# Breadboard_Breakout_Module.net
KiCad netlist of a schematic drawn in EAGLE
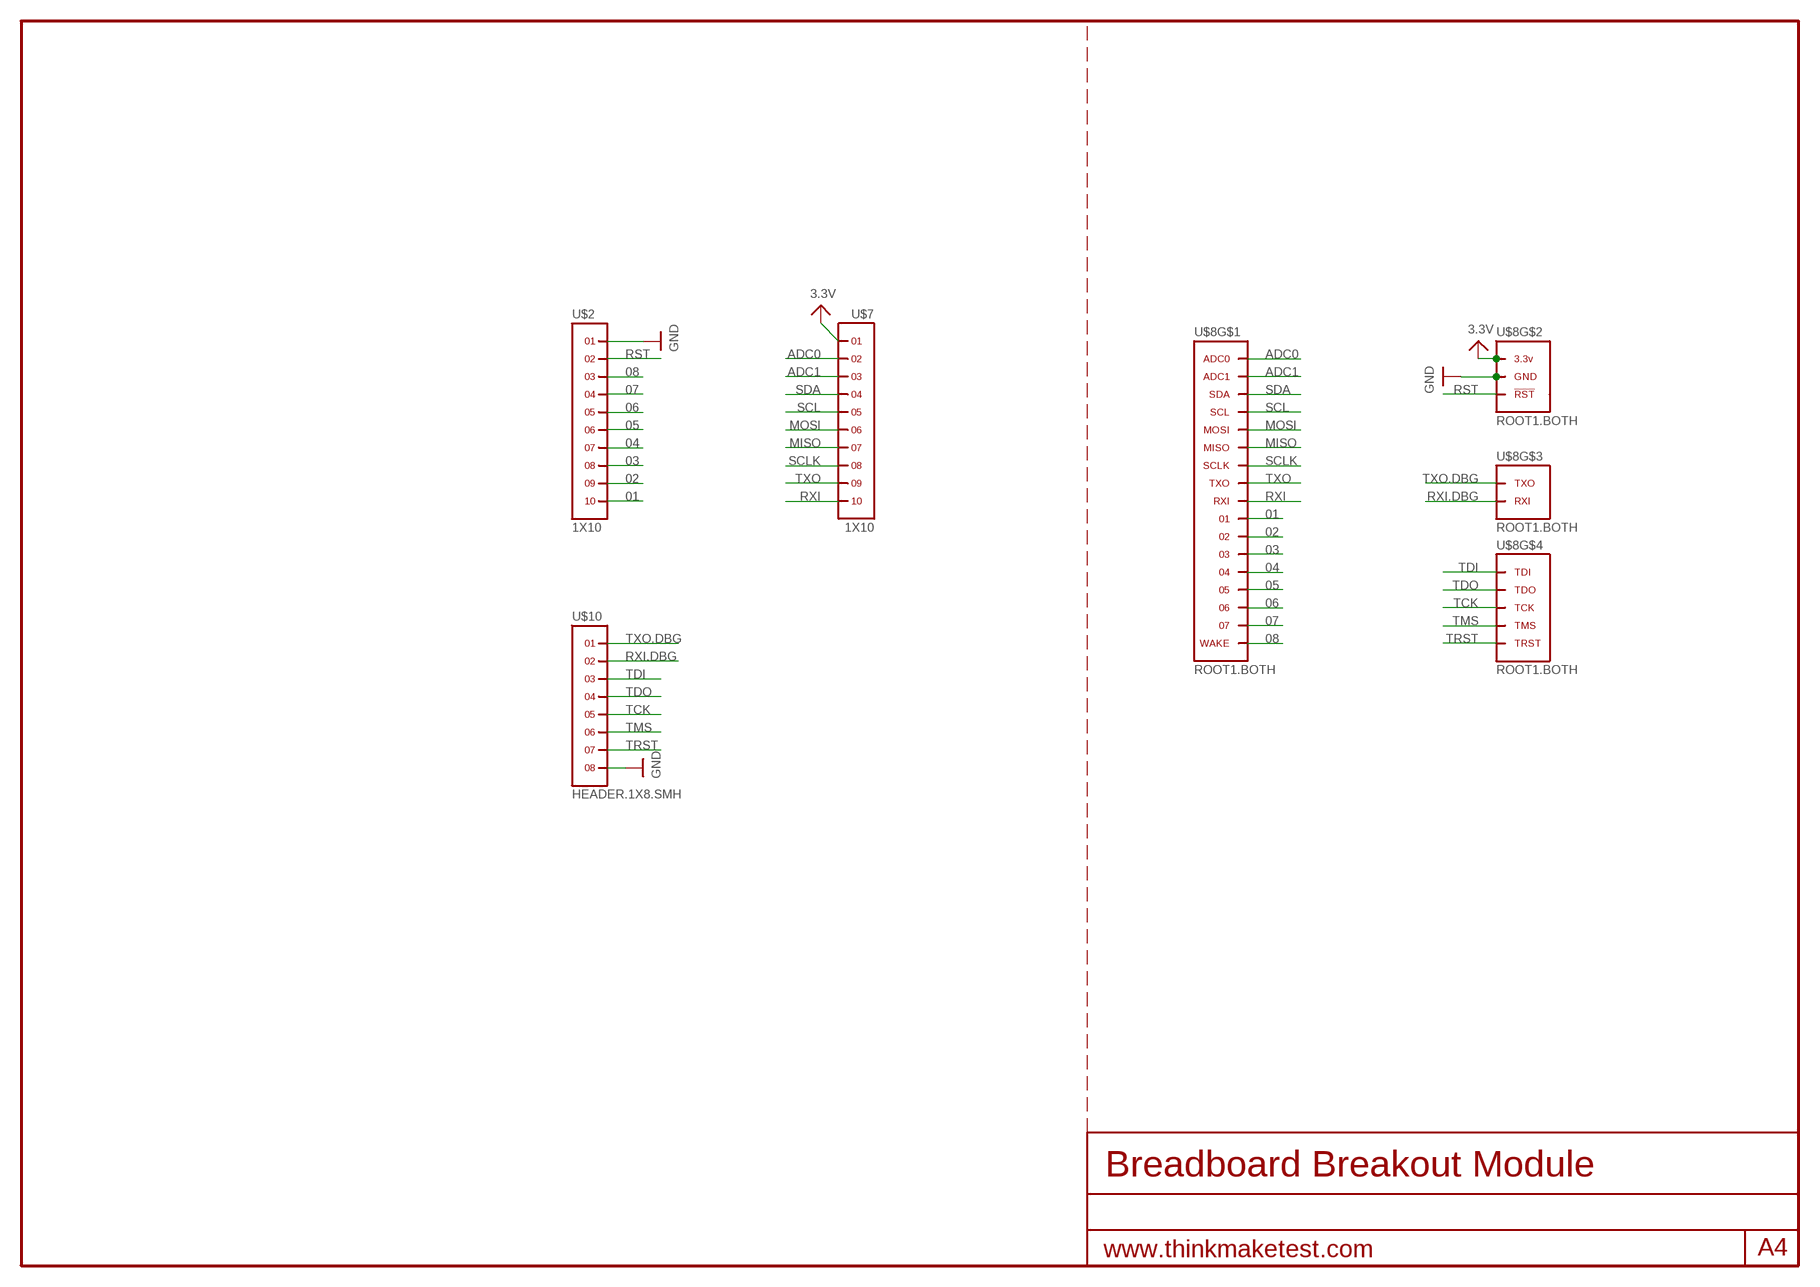
[diagram p0: schematic, sheet 1]

(export (version "E")
  (design (tool "Eeschema 10.0.6"))
  (components
    (comp (ref "U$2")
      (value "1X10")
      (footprint "eagle-import:1X10")
      (libsource (lib "eagle-import") (part "1X10"))
    )
    (comp (ref "U$7")
      (value "1X10")
      (footprint "eagle-import:1X10")
      (libsource (lib "eagle-import") (part "1X10"))
    )
    (comp (ref "U$8")
      (value "ROOT1.BOTH")
      (footprint "eagle-import:ROOT1.BOTH")
      (libsource (lib "eagle-import") (part "ROOT1.BOTH"))
    )
    (comp (ref "U$10")
      (value "HEADER.1X8.SMH")
      (footprint "eagle-import:SMH-108-XX-X-S")
      (libsource (lib "eagle-import") (part "HEADER.1X8.SMH"))
    )
  )
  (nets
    (net (code "1") (name "/01") (class "Default")
      (node (ref "U$2") (pin "10") (pinfunction "10_10") (pintype "bidirectional"))
      (node (ref "U$8") (pin "01") (pinfunction "01_01") (pintype "bidirectional"))
      (node (ref "U$8") (pin "01@1") (pinfunction "01_01@1") (pintype "bidirectional"))
      (node (ref "U$8") (pin "01@VIA") (pinfunction "01_01@VIA") (pintype "bidirectional"))
    )
    (net (code "2") (name "/02") (class "Default")
      (node (ref "U$2") (pin "9") (pinfunction "9_9") (pintype "bidirectional"))
      (node (ref "U$8") (pin "02") (pinfunction "02_02") (pintype "bidirectional"))
      (node (ref "U$8") (pin "02@1") (pinfunction "02_02@1") (pintype "bidirectional"))
      (node (ref "U$8") (pin "02@VIA") (pinfunction "02_02@VIA") (pintype "bidirectional"))
    )
    (net (code "3") (name "/03") (class "Default")
      (node (ref "U$2") (pin "8") (pinfunction "8_8") (pintype "bidirectional"))
      (node (ref "U$8") (pin "03") (pinfunction "03_03") (pintype "bidirectional"))
      (node (ref "U$8") (pin "03@1") (pinfunction "03_03@1") (pintype "bidirectional"))
      (node (ref "U$8") (pin "03@VIA") (pinfunction "03_03@VIA") (pintype "bidirectional"))
    )
    (net (code "4") (name "/04") (class "Default")
      (node (ref "U$2") (pin "7") (pinfunction "7_7") (pintype "bidirectional"))
      (node (ref "U$8") (pin "04") (pinfunction "04_04") (pintype "bidirectional"))
      (node (ref "U$8") (pin "04@1") (pinfunction "04_04@1") (pintype "bidirectional"))
      (node (ref "U$8") (pin "04@VIA") (pinfunction "04_04@VIA") (pintype "bidirectional"))
    )
    (net (code "5") (name "/05") (class "Default")
      (node (ref "U$2") (pin "6") (pinfunction "6_6") (pintype "bidirectional"))
      (node (ref "U$8") (pin "05") (pinfunction "05_05") (pintype "bidirectional"))
      (node (ref "U$8") (pin "05@1") (pinfunction "05_05@1") (pintype "bidirectional"))
      (node (ref "U$8") (pin "05@VIA") (pinfunction "05_05@VIA") (pintype "bidirectional"))
    )
    (net (code "6") (name "/06") (class "Default")
      (node (ref "U$2") (pin "5") (pinfunction "5_5") (pintype "bidirectional"))
      (node (ref "U$8") (pin "06") (pinfunction "06_06") (pintype "bidirectional"))
      (node (ref "U$8") (pin "06@1") (pinfunction "06_06@1") (pintype "bidirectional"))
      (node (ref "U$8") (pin "06@VIA") (pinfunction "06_06@VIA") (pintype "bidirectional"))
    )
    (net (code "7") (name "/07") (class "Default")
      (node (ref "U$2") (pin "4") (pinfunction "4_4") (pintype "bidirectional"))
      (node (ref "U$8") (pin "07") (pinfunction "07_07") (pintype "bidirectional"))
      (node (ref "U$8") (pin "07@1") (pinfunction "07_07@1") (pintype "bidirectional"))
      (node (ref "U$8") (pin "07@VIA") (pinfunction "07_07@VIA") (pintype "bidirectional"))
    )
    (net (code "8") (name "/08") (class "Default")
      (node (ref "U$2") (pin "3") (pinfunction "3_3") (pintype "bidirectional"))
      (node (ref "U$8") (pin "WAKE") (pinfunction "WAKE_WAKE") (pintype "bidirectional"))
      (node (ref "U$8") (pin "WAKE@1") (pinfunction "WAKE_WAKE@1") (pintype "bidirectional"))
      (node (ref "U$8") (pin "WAKE@VIA") (pinfunction "WAKE_WAKE@VIA") (pintype "bidirectional"))
    )
    (net (code "9") (name "/ADC0") (class "Default")
      (node (ref "U$7") (pin "2") (pinfunction "2_2") (pintype "bidirectional"))
      (node (ref "U$8") (pin "ADC0") (pinfunction "ADC0_ADC0") (pintype "bidirectional"))
      (node (ref "U$8") (pin "ADC0@1") (pinfunction "ADC0_ADC0@1") (pintype "bidirectional"))
      (node (ref "U$8") (pin "ADC0@VIA") (pinfunction "ADC0_ADC0@VIA") (pintype "bidirectional"))
    )
    (net (code "10") (name "/ADC1") (class "Default")
      (node (ref "U$7") (pin "3") (pinfunction "3_3") (pintype "bidirectional"))
      (node (ref "U$8") (pin "ADC1") (pinfunction "ADC1_ADC1") (pintype "bidirectional"))
      (node (ref "U$8") (pin "ADC1@1") (pinfunction "ADC1_ADC1@1") (pintype "bidirectional"))
      (node (ref "U$8") (pin "ADC1@VIA") (pinfunction "ADC1_ADC1@VIA") (pintype "bidirectional"))
    )
    (net (code "11") (name "/MISO") (class "Default")
      (node (ref "U$7") (pin "7") (pinfunction "7_7") (pintype "bidirectional"))
      (node (ref "U$8") (pin "MISO") (pinfunction "MISO_MISO") (pintype "bidirectional"))
      (node (ref "U$8") (pin "MISO@1") (pinfunction "MISO_MISO@1") (pintype "bidirectional"))
      (node (ref "U$8") (pin "MISO@VIA") (pinfunction "MISO_MISO@VIA") (pintype "bidirectional"))
    )
    (net (code "12") (name "/MOSI") (class "Default")
      (node (ref "U$7") (pin "6") (pinfunction "6_6") (pintype "bidirectional"))
      (node (ref "U$8") (pin "MOSI") (pinfunction "MOSI_MOSI") (pintype "bidirectional"))
      (node (ref "U$8") (pin "MOSI@1") (pinfunction "MOSI_MOSI@1") (pintype "bidirectional"))
      (node (ref "U$8") (pin "MOSI@VIA") (pinfunction "MOSI_MOSI@VIA") (pintype "bidirectional"))
    )
    (net (code "13") (name "/RST") (class "Default")
      (node (ref "U$2") (pin "2") (pinfunction "2_2") (pintype "bidirectional"))
      (node (ref "U$8") (pin "RST") (pinfunction "~{RST}_RST") (pintype "bidirectional"))
      (node (ref "U$8") (pin "RST@1") (pinfunction "~{RST}_RST@1") (pintype "bidirectional"))
      (node (ref "U$8") (pin "RST@VIA") (pinfunction "~{RST}_RST@VIA") (pintype "bidirectional"))
    )
    (net (code "14") (name "/RXI") (class "Default")
      (node (ref "U$7") (pin "10") (pinfunction "10_10") (pintype "bidirectional"))
      (node (ref "U$8") (pin "RXI") (pinfunction "RXI_RXI") (pintype "bidirectional"))
      (node (ref "U$8") (pin "RXI@1") (pinfunction "RXI_RXI@1") (pintype "bidirectional"))
      (node (ref "U$8") (pin "RXI@VIA") (pinfunction "RXI_RXI@VIA") (pintype "bidirectional"))
    )
    (net (code "15") (name "/RXI.DBG") (class "Default")
      (node (ref "U$10") (pin "2") (pinfunction "2_2") (pintype "bidirectional"))
      (node (ref "U$8") (pin "RXI.DBG") (pinfunction "RXI_RXI.DBG") (pintype "bidirectional"))
      (node (ref "U$8") (pin "RXI.DBG@1") (pinfunction "RXI_RXI.DBG@1") (pintype "bidirectional"))
      (node (ref "U$8") (pin "RXI.DBG@VIA") (pinfunction "RXI_RXI.DBG@VIA") (pintype "bidirectional"))
    )
    (net (code "16") (name "/SCL") (class "Default")
      (node (ref "U$7") (pin "5") (pinfunction "5_5") (pintype "bidirectional"))
      (node (ref "U$8") (pin "SCL") (pinfunction "SCL_SCL") (pintype "bidirectional"))
      (node (ref "U$8") (pin "SCL@1") (pinfunction "SCL_SCL@1") (pintype "bidirectional"))
      (node (ref "U$8") (pin "SCL@VIA") (pinfunction "SCL_SCL@VIA") (pintype "bidirectional"))
    )
    (net (code "17") (name "/SCLK") (class "Default")
      (node (ref "U$7") (pin "8") (pinfunction "8_8") (pintype "bidirectional"))
      (node (ref "U$8") (pin "SCLK") (pinfunction "SCLK_SCLK") (pintype "bidirectional"))
      (node (ref "U$8") (pin "SCLK@1") (pinfunction "SCLK_SCLK@1") (pintype "bidirectional"))
      (node (ref "U$8") (pin "SCLK@VIA") (pinfunction "SCLK_SCLK@VIA") (pintype "bidirectional"))
    )
    (net (code "18") (name "/SDA") (class "Default")
      (node (ref "U$7") (pin "4") (pinfunction "4_4") (pintype "bidirectional"))
      (node (ref "U$8") (pin "SDA") (pinfunction "SDA_SDA") (pintype "bidirectional"))
      (node (ref "U$8") (pin "SDA@1") (pinfunction "SDA_SDA@1") (pintype "bidirectional"))
      (node (ref "U$8") (pin "SDA@VIA") (pinfunction "SDA_SDA@VIA") (pintype "bidirectional"))
    )
    (net (code "19") (name "/TCK") (class "Default")
      (node (ref "U$10") (pin "5") (pinfunction "5_5") (pintype "bidirectional"))
      (node (ref "U$8") (pin "TCK") (pinfunction "TCK_TCK") (pintype "bidirectional"))
      (node (ref "U$8") (pin "TCK@1") (pinfunction "TCK_TCK@1") (pintype "bidirectional"))
      (node (ref "U$8") (pin "TCK@VIA") (pinfunction "TCK_TCK@VIA") (pintype "bidirectional"))
    )
    (net (code "20") (name "/TDI") (class "Default")
      (node (ref "U$10") (pin "3") (pinfunction "3_3") (pintype "bidirectional"))
      (node (ref "U$8") (pin "TDI") (pinfunction "TDI_TDI") (pintype "bidirectional"))
      (node (ref "U$8") (pin "TDI@1") (pinfunction "TDI_TDI@1") (pintype "bidirectional"))
      (node (ref "U$8") (pin "TDI@VIA") (pinfunction "TDI_TDI@VIA") (pintype "bidirectional"))
    )
    (net (code "21") (name "/TDO") (class "Default")
      (node (ref "U$10") (pin "4") (pinfunction "4_4") (pintype "bidirectional"))
      (node (ref "U$8") (pin "TDO") (pinfunction "TDO_TDO") (pintype "bidirectional"))
      (node (ref "U$8") (pin "TDO@1") (pinfunction "TDO_TDO@1") (pintype "bidirectional"))
      (node (ref "U$8") (pin "TDO@VIA") (pinfunction "TDO_TDO@VIA") (pintype "bidirectional"))
    )
    (net (code "22") (name "/TMS") (class "Default")
      (node (ref "U$10") (pin "6") (pinfunction "6_6") (pintype "bidirectional"))
      (node (ref "U$8") (pin "TMS") (pinfunction "TMS_TMS") (pintype "bidirectional"))
      (node (ref "U$8") (pin "TMS@1") (pinfunction "TMS_TMS@1") (pintype "bidirectional"))
      (node (ref "U$8") (pin "TMS@VIA") (pinfunction "TMS_TMS@VIA") (pintype "bidirectional"))
    )
    (net (code "23") (name "/TRST") (class "Default")
      (node (ref "U$10") (pin "7") (pinfunction "7_7") (pintype "bidirectional"))
      (node (ref "U$8") (pin "TRST") (pinfunction "TRST_TRST") (pintype "bidirectional"))
      (node (ref "U$8") (pin "TRST@1") (pinfunction "TRST_TRST@1") (pintype "bidirectional"))
      (node (ref "U$8") (pin "TRST@VIA") (pinfunction "TRST_TRST@VIA") (pintype "bidirectional"))
    )
    (net (code "24") (name "/TXO") (class "Default")
      (node (ref "U$7") (pin "9") (pinfunction "9_9") (pintype "bidirectional"))
      (node (ref "U$8") (pin "TXO") (pinfunction "TXO_TXO") (pintype "bidirectional"))
      (node (ref "U$8") (pin "TXO@1") (pinfunction "TXO_TXO@1") (pintype "bidirectional"))
      (node (ref "U$8") (pin "TXO@VIA") (pinfunction "TXO_TXO@VIA") (pintype "bidirectional"))
    )
    (net (code "25") (name "/TXO.DBG") (class "Default")
      (node (ref "U$10") (pin "1") (pinfunction "1_1") (pintype "bidirectional"))
      (node (ref "U$8") (pin "TXO.DBG") (pinfunction "TXO_TXO.DBG") (pintype "bidirectional"))
      (node (ref "U$8") (pin "TXO.DBG@1") (pinfunction "TXO_TXO.DBG@1") (pintype "bidirectional"))
      (node (ref "U$8") (pin "TXO.DBG@VIA") (pinfunction "TXO_TXO.DBG@VIA") (pintype "bidirectional"))
    )
    (net (code "26") (name "3.3V") (class "Default")
      (node (ref "U$7") (pin "1") (pinfunction "1_1") (pintype "bidirectional"))
      (node (ref "U$8") (pin "3.3V@1") (pinfunction "3.3V_3.3V@1") (pintype "bidirectional"))
      (node (ref "U$8") (pin "3.3V@10") (pinfunction "3.3V_3.3V@10") (pintype "bidirectional"))
      (node (ref "U$8") (pin "3.3V@11") (pinfunction "3.3V_3.3V@11") (pintype "bidirectional"))
      (node (ref "U$8") (pin "3.3V@12") (pinfunction "3.3V_3.3V@12") (pintype "bidirectional"))
      (node (ref "U$8") (pin "3.3V@13") (pinfunction "3.3V_3.3V@13") (pintype "bidirectional"))
      (node (ref "U$8") (pin "3.3V@14") (pinfunction "3.3V_3.3V@14") (pintype "bidirectional"))
      (node (ref "U$8") (pin "3.3V@15") (pinfunction "3.3V_3.3V@15") (pintype "bidirectional"))
      (node (ref "U$8") (pin "3.3V@16") (pinfunction "3.3V_3.3V@16") (pintype "bidirectional"))
      (node (ref "U$8") (pin "3.3V@17") (pinfunction "3.3V_3.3V@17") (pintype "bidirectional"))
      (node (ref "U$8") (pin "3.3V@18") (pinfunction "3.3V_3.3V@18") (pintype "bidirectional"))
      (node (ref "U$8") (pin "3.3V@19") (pinfunction "3.3V_3.3V@19") (pintype "bidirectional"))
      (node (ref "U$8") (pin "3.3V@2") (pinfunction "3.3V_3.3V@2") (pintype "bidirectional"))
      (node (ref "U$8") (pin "3.3V@20") (pinfunction "3.3V_3.3V@20") (pintype "bidirectional"))
      (node (ref "U$8") (pin "3.3V@21") (pinfunction "3.3V_3.3V@21") (pintype "bidirectional"))
      (node (ref "U$8") (pin "3.3V@22") (pinfunction "3.3V_3.3V@22") (pintype "bidirectional"))
      (node (ref "U$8") (pin "3.3V@23") (pinfunction "3.3V_3.3V@23") (pintype "bidirectional"))
      (node (ref "U$8") (pin "3.3V@24") (pinfunction "3.3V_3.3V@24") (pintype "bidirectional"))
      (node (ref "U$8") (pin "3.3V@3") (pinfunction "3.3V_3.3V@3") (pintype "bidirectional"))
      (node (ref "U$8") (pin "3.3V@4") (pinfunction "3.3V_3.3V@4") (pintype "bidirectional"))
      (node (ref "U$8") (pin "3.3V@5") (pinfunction "3.3V_3.3V@5") (pintype "bidirectional"))
      (node (ref "U$8") (pin "3.3V@6") (pinfunction "3.3V_3.3V@6") (pintype "bidirectional"))
      (node (ref "U$8") (pin "3.3V@7") (pinfunction "3.3V_3.3V@7") (pintype "bidirectional"))
      (node (ref "U$8") (pin "3.3V@8") (pinfunction "3.3V_3.3V@8") (pintype "bidirectional"))
      (node (ref "U$8") (pin "3.3V@9") (pinfunction "3.3V_3.3V@9") (pintype "bidirectional"))
      (node (ref "U$8") (pin "3.3V@VIA") (pinfunction "3.3V_3.3V@VIA") (pintype "bidirectional"))
    )
    (net (code "27") (name "GND") (class "Default")
      (node (ref "U$10") (pin "8") (pinfunction "8_8") (pintype "bidirectional"))
      (node (ref "U$2") (pin "1") (pinfunction "1_1") (pintype "bidirectional"))
      (node (ref "U$8") (pin "GND@1") (pinfunction "GND_GND@1") (pintype "bidirectional"))
      (node (ref "U$8") (pin "GND@10") (pinfunction "GND_GND@10") (pintype "bidirectional"))
      (node (ref "U$8") (pin "GND@11") (pinfunction "GND_GND@11") (pintype "bidirectional"))
      (node (ref "U$8") (pin "GND@12") (pinfunction "GND_GND@12") (pintype "bidirectional"))
      (node (ref "U$8") (pin "GND@13") (pinfunction "GND_GND@13") (pintype "bidirectional"))
      (node (ref "U$8") (pin "GND@14") (pinfunction "GND_GND@14") (pintype "bidirectional"))
      (node (ref "U$8") (pin "GND@15") (pinfunction "GND_GND@15") (pintype "bidirectional"))
      (node (ref "U$8") (pin "GND@16") (pinfunction "GND_GND@16") (pintype "bidirectional"))
      (node (ref "U$8") (pin "GND@17") (pinfunction "GND_GND@17") (pintype "bidirectional"))
      (node (ref "U$8") (pin "GND@18") (pinfunction "GND_GND@18") (pintype "bidirectional"))
      (node (ref "U$8") (pin "GND@19") (pinfunction "GND_GND@19") (pintype "bidirectional"))
      (node (ref "U$8") (pin "GND@2") (pinfunction "GND_GND@2") (pintype "bidirectional"))
      (node (ref "U$8") (pin "GND@20") (pinfunction "GND_GND@20") (pintype "bidirectional"))
      (node (ref "U$8") (pin "GND@21") (pinfunction "GND_GND@21") (pintype "bidirectional"))
      (node (ref "U$8") (pin "GND@22") (pinfunction "GND_GND@22") (pintype "bidirectional"))
      (node (ref "U$8") (pin "GND@23") (pinfunction "GND_GND@23") (pintype "bidirectional"))
      (node (ref "U$8") (pin "GND@24") (pinfunction "GND_GND@24") (pintype "bidirectional"))
      (node (ref "U$8") (pin "GND@25") (pinfunction "GND_GND@25") (pintype "bidirectional"))
      (node (ref "U$8") (pin "GND@26") (pinfunction "GND_GND@26") (pintype "bidirectional"))
      (node (ref "U$8") (pin "GND@3") (pinfunction "GND_GND@3") (pintype "bidirectional"))
      (node (ref "U$8") (pin "GND@4") (pinfunction "GND_GND@4") (pintype "bidirectional"))
      (node (ref "U$8") (pin "GND@5") (pinfunction "GND_GND@5") (pintype "bidirectional"))
      (node (ref "U$8") (pin "GND@6") (pinfunction "GND_GND@6") (pintype "bidirectional"))
      (node (ref "U$8") (pin "GND@7") (pinfunction "GND_GND@7") (pintype "bidirectional"))
      (node (ref "U$8") (pin "GND@8") (pinfunction "GND_GND@8") (pintype "bidirectional"))
      (node (ref "U$8") (pin "GND@9") (pinfunction "GND_GND@9") (pintype "bidirectional"))
      (node (ref "U$8") (pin "GND@VIA") (pinfunction "GND_GND@VIA") (pintype "bidirectional"))
    )
  )
)
